# nigme2_Crocodile.net
KiCad netlist of a schematic drawn in Altium Designer
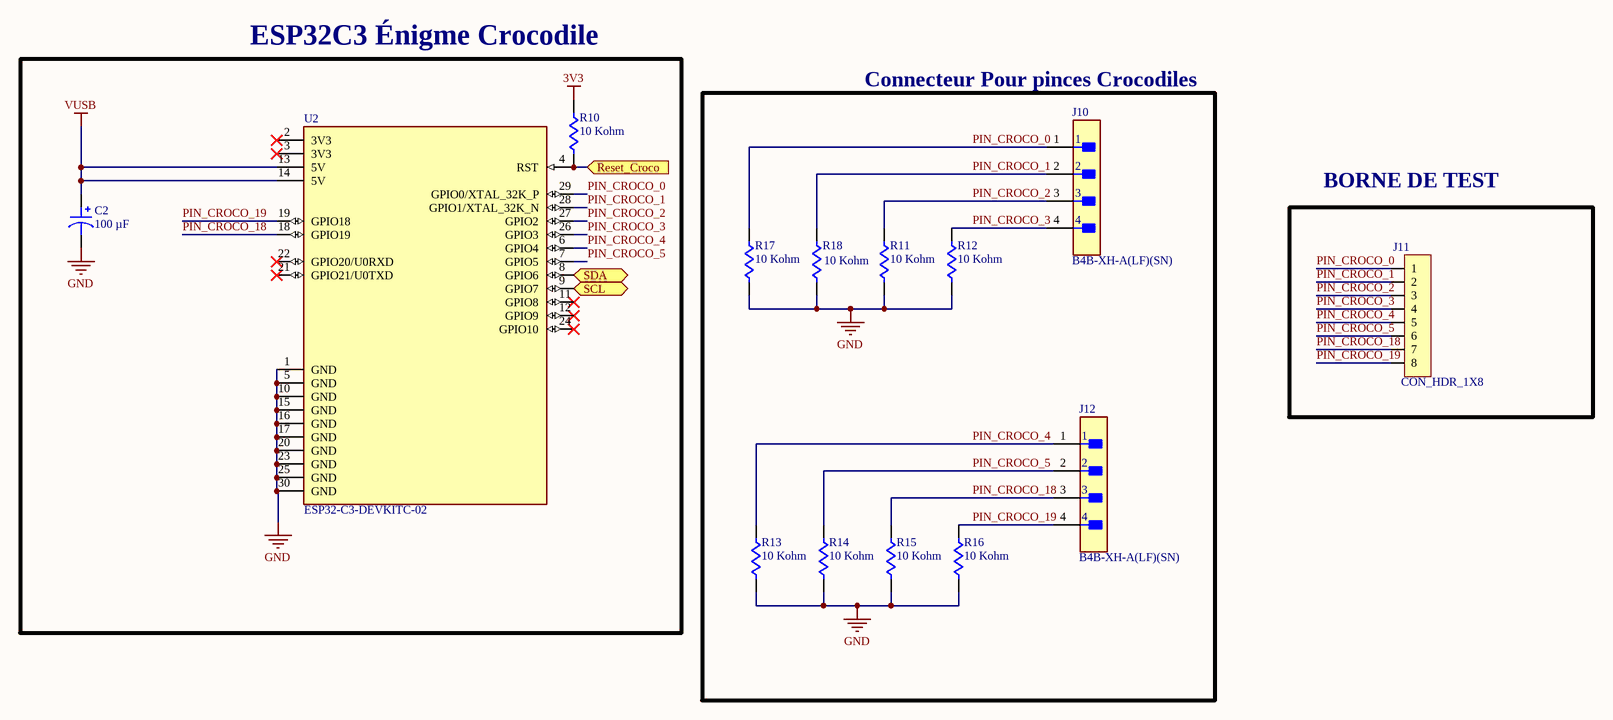
[diagram p0: Énigme2_Crocodile.SchDoc]

(export (version "E")
  (design (tool "Eeschema 10.0.6"))
  (components
    (comp (ref "C2")
      (value "100 µF")
      (footprint "CAP AL TH D8 L3.5 H12.5")
      (description "CAP ALUM 100UF 20% 50V RADIAL")
      (fields (field (name "PART NUMBER") "860020674015") (field (name "MANUFACTURER") "Würth Elektronik"))
      (libsource (lib "Celestial Altium Library - altium_library") (part "Polarised Capacitor"))
    )
    (comp (ref "J10")
      (value "B4B-XH-A(LF)(SN)")
      (footprint "FP-B4B-XH-A_LF_SN-MFG")
      (description "CONN HEADER VERT 4POS 2.5MM")
      (libsource (lib "Altium Content Vault") (part "299a8cea1bdcbc3624fe62c390fa72c"))
    )
    (comp (ref "J11")
      (value "CON_HDR_1X8")
      (footprint "CON_HDR_1x8")
      (description "CON - Header 1X8 pins, 100Mils - TH-8")
      (fields (field (name "SOURCE") "CEGEP_SHERBROOKE_TGE_LIBRARY.SchLib"))
      (libsource (lib "Cegep de Sherbrooke") (part "CON_HDR_1X8"))
    )
    (comp (ref "J12")
      (value "B4B-XH-A(LF)(SN)")
      (footprint "FP-B4B-XH-A_LF_SN-MFG")
      (description "CONN HEADER VERT 4POS 2.5MM")
      (libsource (lib "Altium Content Vault") (part "299a8cea1bdcbc3624fe62c390fa72c"))
    )
    (comp (ref "R10")
      (value "10 Kohm")
      (footprint "Res_Template")
      (description "Custom Semiconductor Resistor")
      (libsource (lib "Schlib1") (part "470 ohm"))
    )
    (comp (ref "R11")
      (value "10 Kohm")
      (footprint "Res_Template")
      (description "Custom Semiconductor Resistor")
      (libsource (lib "Schlib1") (part "470 ohm"))
    )
    (comp (ref "R12")
      (value "10 Kohm")
      (footprint "Res_Template")
      (description "Custom Semiconductor Resistor")
      (libsource (lib "Schlib1") (part "470 ohm"))
    )
    (comp (ref "R13")
      (value "10 Kohm")
      (footprint "Res_Template")
      (description "Custom Semiconductor Resistor")
      (libsource (lib "Schlib1") (part "470 ohm"))
    )
    (comp (ref "R14")
      (value "10 Kohm")
      (footprint "Res_Template")
      (description "Custom Semiconductor Resistor")
      (libsource (lib "Schlib1") (part "470 ohm"))
    )
    (comp (ref "R15")
      (value "10 Kohm")
      (footprint "Res_Template")
      (description "Custom Semiconductor Resistor")
      (libsource (lib "Schlib1") (part "470 ohm"))
    )
    (comp (ref "R16")
      (value "10 Kohm")
      (footprint "Res_Template")
      (description "Custom Semiconductor Resistor")
      (libsource (lib "Schlib1") (part "470 ohm"))
    )
    (comp (ref "R17")
      (value "10 Kohm")
      (footprint "Res_Template")
      (description "Custom Semiconductor Resistor")
      (libsource (lib "Schlib1") (part "470 ohm"))
    )
    (comp (ref "R18")
      (value "10 Kohm")
      (footprint "Res_Template")
      (description "Custom Semiconductor Resistor")
      (libsource (lib "Schlib1") (part "470 ohm"))
    )
    (comp (ref "U2")
      (value "ESP32-C3-DEVKITC-02")
      (footprint "XCVR_ESP32-C3-DEVKITC-02")
      (fields (field (name "MP") "ESP32-C3-DevKitC-02") (field (name "MF") "Espressif Systems"))
      (libsource (lib "ESP32-C3-DEVKITC-02") (part "ESP32-C3-DEVKITC-02"))
    )
  )
  (nets
    (net (code "1") (name "/PIN_CROCO_0") (class "Default")
      (node (ref "J10") (pin "1") (pinfunction "1_1") (pintype "passive"))
      (node (ref "J11") (pin "1") (pinfunction "1_1") (pintype "passive"))
      (node (ref "R17") (pin "2") (pinfunction "2_2") (pintype "passive"))
      (node (ref "U2") (pin "29") (pinfunction "GPIO0/XTAL_32K_P_29") (pintype "bidirectional"))
    )
    (net (code "2") (name "/PIN_CROCO_1") (class "Default")
      (node (ref "J10") (pin "2") (pinfunction "2_2") (pintype "passive"))
      (node (ref "J11") (pin "2") (pinfunction "2_2") (pintype "passive"))
      (node (ref "R18") (pin "2") (pinfunction "2_2") (pintype "passive"))
      (node (ref "U2") (pin "28") (pinfunction "GPIO1/XTAL_32K_N_28") (pintype "bidirectional"))
    )
    (net (code "3") (name "/PIN_CROCO_2") (class "Default")
      (node (ref "J10") (pin "3") (pinfunction "3_3") (pintype "passive"))
      (node (ref "J11") (pin "3") (pinfunction "3_3") (pintype "passive"))
      (node (ref "R11") (pin "2") (pinfunction "2_2") (pintype "passive"))
      (node (ref "U2") (pin "27") (pinfunction "GPIO2_27") (pintype "bidirectional"))
    )
    (net (code "4") (name "/PIN_CROCO_3") (class "Default")
      (node (ref "J10") (pin "4") (pinfunction "4_4") (pintype "passive"))
      (node (ref "J11") (pin "4") (pinfunction "4_4") (pintype "passive"))
      (node (ref "R12") (pin "2") (pinfunction "2_2") (pintype "passive"))
      (node (ref "U2") (pin "26") (pinfunction "GPIO3_26") (pintype "bidirectional"))
    )
    (net (code "5") (name "/PIN_CROCO_4") (class "Default")
      (node (ref "J11") (pin "5") (pinfunction "5_5") (pintype "passive"))
      (node (ref "J12") (pin "1") (pinfunction "1_1") (pintype "passive"))
      (node (ref "R13") (pin "2") (pinfunction "2_2") (pintype "passive"))
      (node (ref "U2") (pin "6") (pinfunction "GPIO4_6") (pintype "bidirectional"))
    )
    (net (code "6") (name "/PIN_CROCO_5") (class "Default")
      (node (ref "J11") (pin "6") (pinfunction "6_6") (pintype "passive"))
      (node (ref "J12") (pin "2") (pinfunction "2_2") (pintype "passive"))
      (node (ref "R14") (pin "2") (pinfunction "2_2") (pintype "passive"))
      (node (ref "U2") (pin "7") (pinfunction "GPIO5_7") (pintype "bidirectional"))
    )
    (net (code "7") (name "/PIN_CROCO_18") (class "Default")
      (node (ref "J11") (pin "7") (pinfunction "7_7") (pintype "passive"))
      (node (ref "J12") (pin "3") (pinfunction "3_3") (pintype "passive"))
      (node (ref "R15") (pin "2") (pinfunction "2_2") (pintype "passive"))
      (node (ref "U2") (pin "18") (pinfunction "GPIO19_18") (pintype "bidirectional"))
    )
    (net (code "8") (name "/PIN_CROCO_19") (class "Default")
      (node (ref "J11") (pin "8") (pinfunction "8_8") (pintype "passive"))
      (node (ref "J12") (pin "4") (pinfunction "4_4") (pintype "passive"))
      (node (ref "R16") (pin "2") (pinfunction "2_2") (pintype "passive"))
      (node (ref "U2") (pin "19") (pinfunction "GPIO18_19") (pintype "bidirectional"))
    )
    (net (code "9") (name "/Reset_Croco") (class "Default")
      (node (ref "R10") (pin "1") (pinfunction "1_1") (pintype "passive"))
      (node (ref "U2") (pin "4") (pinfunction "RST_4") (pintype "input"))
    )
    (net (code "10") (name "/SCL") (class "Default")
      (node (ref "U2") (pin "9") (pinfunction "GPIO7_9") (pintype "bidirectional"))
    )
    (net (code "11") (name "/SDA") (class "Default")
      (node (ref "U2") (pin "8") (pinfunction "GPIO6_8") (pintype "bidirectional"))
    )
    (net (code "12") (name "3V3") (class "Default")
      (node (ref "R10") (pin "2") (pinfunction "2_2") (pintype "passive"))
    )
    (net (code "13") (name "GND") (class "Default")
      (node (ref "C2") (pin "2") (pinfunction "2_2") (pintype "passive"))
      (node (ref "R11") (pin "1") (pinfunction "1_1") (pintype "passive"))
      (node (ref "R12") (pin "1") (pinfunction "1_1") (pintype "passive"))
      (node (ref "R13") (pin "1") (pinfunction "1_1") (pintype "passive"))
      (node (ref "R14") (pin "1") (pinfunction "1_1") (pintype "passive"))
      (node (ref "R15") (pin "1") (pinfunction "1_1") (pintype "passive"))
      (node (ref "R16") (pin "1") (pinfunction "1_1") (pintype "passive"))
      (node (ref "R17") (pin "1") (pinfunction "1_1") (pintype "passive"))
      (node (ref "R18") (pin "1") (pinfunction "1_1") (pintype "passive"))
      (node (ref "U2") (pin "1") (pinfunction "GND_1") (pintype "power_in"))
      (node (ref "U2") (pin "10") (pinfunction "GND_10") (pintype "power_in"))
      (node (ref "U2") (pin "15") (pinfunction "GND_15") (pintype "power_in"))
      (node (ref "U2") (pin "16") (pinfunction "GND_16") (pintype "power_in"))
      (node (ref "U2") (pin "17") (pinfunction "GND_17") (pintype "power_in"))
      (node (ref "U2") (pin "20") (pinfunction "GND_20") (pintype "power_in"))
      (node (ref "U2") (pin "23") (pinfunction "GND_23") (pintype "power_in"))
      (node (ref "U2") (pin "25") (pinfunction "GND_25") (pintype "power_in"))
      (node (ref "U2") (pin "30") (pinfunction "GND_30") (pintype "power_in"))
      (node (ref "U2") (pin "5") (pinfunction "GND_5") (pintype "power_in"))
    )
    (net (code "14") (name "VUSB") (class "Default")
      (node (ref "C2") (pin "1") (pinfunction "1_1") (pintype "passive"))
      (node (ref "U2") (pin "13") (pinfunction "5V_13") (pintype "power_in"))
      (node (ref "U2") (pin "14") (pinfunction "5V_14") (pintype "power_in"))
    )
    (net (code "15") (name "unconnected-(U2-3V3-Pad2)") (class "Default")
      (node (ref "U2") (pin "2") (pinfunction "3V3_2") (pintype "power_in+no_connect"))
    )
    (net (code "16") (name "unconnected-(U2-3V3-Pad3)") (class "Default")
      (node (ref "U2") (pin "3") (pinfunction "3V3_3") (pintype "power_in+no_connect"))
    )
    (net (code "17") (name "unconnected-(U2-GPIO8-Pad11)") (class "Default")
      (node (ref "U2") (pin "11") (pinfunction "GPIO8_11") (pintype "bidirectional+no_connect"))
    )
    (net (code "18") (name "unconnected-(U2-GPIO9-Pad12)") (class "Default")
      (node (ref "U2") (pin "12") (pinfunction "GPIO9_12") (pintype "bidirectional+no_connect"))
    )
    (net (code "19") (name "unconnected-(U2-GPIO10-Pad24)") (class "Default")
      (node (ref "U2") (pin "24") (pinfunction "GPIO10_24") (pintype "bidirectional+no_connect"))
    )
    (net (code "20") (name "unconnected-(U2-GPIO20{slash}U0RXD-Pad22)") (class "Default")
      (node (ref "U2") (pin "22") (pinfunction "GPIO20/U0RXD_22") (pintype "bidirectional+no_connect"))
    )
    (net (code "21") (name "unconnected-(U2-GPIO21{slash}U0TXD-Pad21)") (class "Default")
      (node (ref "U2") (pin "21") (pinfunction "GPIO21/U0TXD_21") (pintype "bidirectional+no_connect"))
    )
  )
)
